# MACMOD.net
KiCad netlist of a schematic drawn in EAGLE
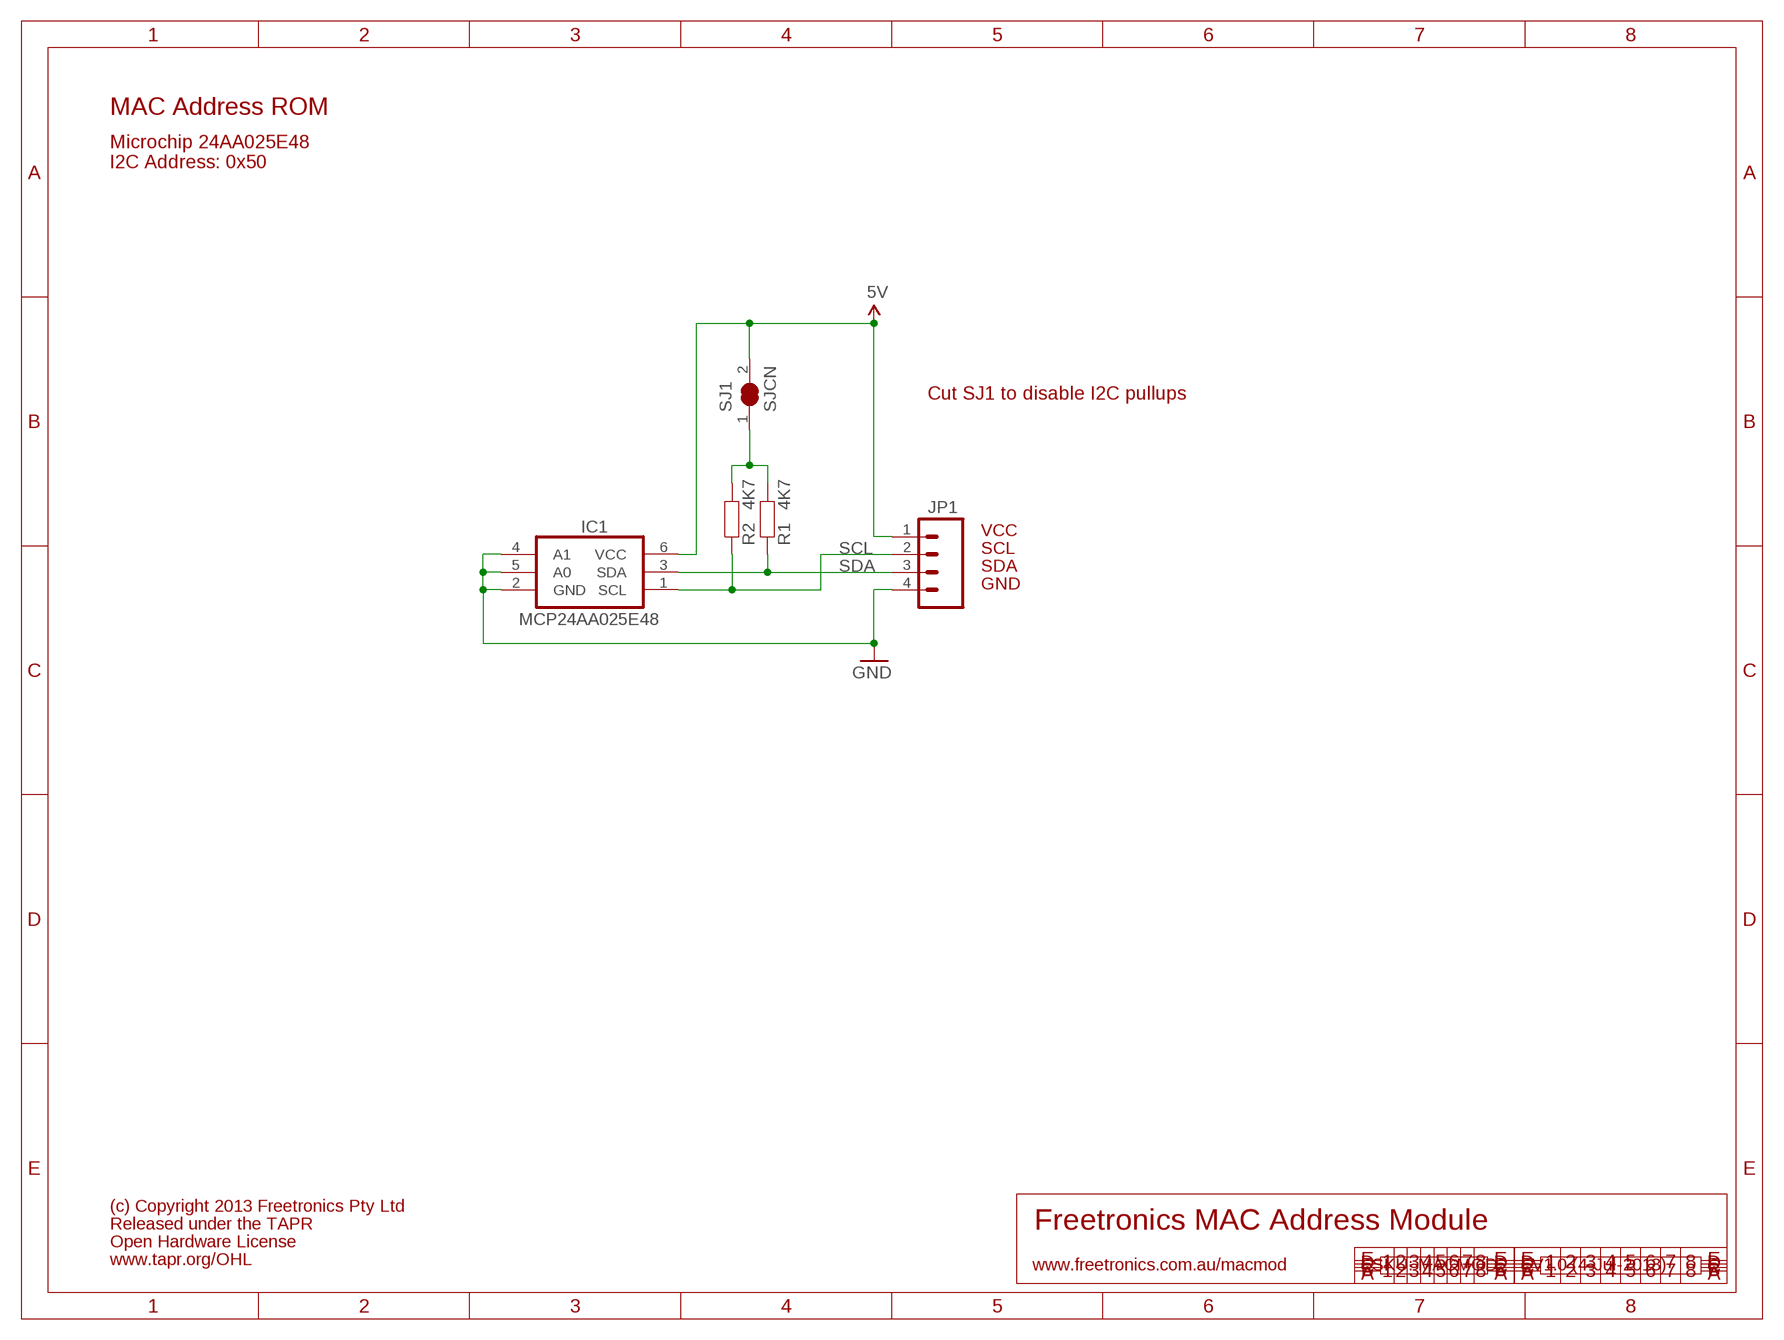
[diagram p0: schematic, sheet 1]

(export (version "E")
  (design (tool "Eeschema 10.0.6"))
  (components
    (comp (ref "IC1")
      (value "MCP24AA025E48")
      (footprint "eagle-import:SOT23-6")
      (libsource (lib "eagle-import") (part "MCP24AA025E48"))
    )
    (comp (ref "JP1")
      (value "M04PTH")
      (footprint "eagle-import:1X04")
      (libsource (lib "eagle-import") (part "M04PTH"))
    )
    (comp (ref "R1")
      (value "4K7")
      (footprint "eagle-import:0603")
      (libsource (lib "eagle-import") (part "RESISTOR0603"))
    )
    (comp (ref "R2")
      (value "4K7")
      (footprint "eagle-import:0603")
      (libsource (lib "eagle-import") (part "RESISTOR0603"))
    )
    (comp (ref "SJ1")
      (value "SJCN")
      (footprint "eagle-import:SJC")
      (libsource (lib "eagle-import") (part "SJCN"))
    )
  )
  (nets
    (net (code "1") (name "/SCL") (class "Default")
      (node (ref "IC1") (pin "1") (pinfunction "SCL_1") (pintype "bidirectional"))
      (node (ref "JP1") (pin "2") (pinfunction "2_2") (pintype "passive"))
      (node (ref "R2") (pin "1") (pinfunction "1_1") (pintype "passive"))
    )
    (net (code "2") (name "/SDA") (class "Default")
      (node (ref "IC1") (pin "3") (pinfunction "SDA_3") (pintype "bidirectional"))
      (node (ref "JP1") (pin "3") (pinfunction "3_3") (pintype "passive"))
      (node (ref "R1") (pin "1") (pinfunction "1_1") (pintype "passive"))
    )
    (net (code "3") (name "5V") (class "Default")
      (node (ref "IC1") (pin "6") (pinfunction "VCC_6") (pintype "power_in"))
      (node (ref "JP1") (pin "1") (pinfunction "1_1") (pintype "passive"))
      (node (ref "SJ1") (pin "2") (pinfunction "2_2") (pintype "passive"))
    )
    (net (code "4") (name "GND") (class "Default")
      (node (ref "IC1") (pin "2") (pinfunction "GND_2") (pintype "power_in"))
      (node (ref "IC1") (pin "4") (pinfunction "A1_4") (pintype "input"))
      (node (ref "IC1") (pin "5") (pinfunction "A0_5") (pintype "input"))
      (node (ref "JP1") (pin "4") (pinfunction "4_4") (pintype "passive"))
    )
    (net (code "5") (name "Net-(R1-Pad2)") (class "Default")
      (node (ref "R1") (pin "2") (pinfunction "2_2") (pintype "passive"))
      (node (ref "R2") (pin "2") (pinfunction "2_2") (pintype "passive"))
      (node (ref "SJ1") (pin "1") (pinfunction "1_1") (pintype "passive"))
    )
  )
)
